# Board.net
KiCad netlist of a schematic drawn in EAGLE
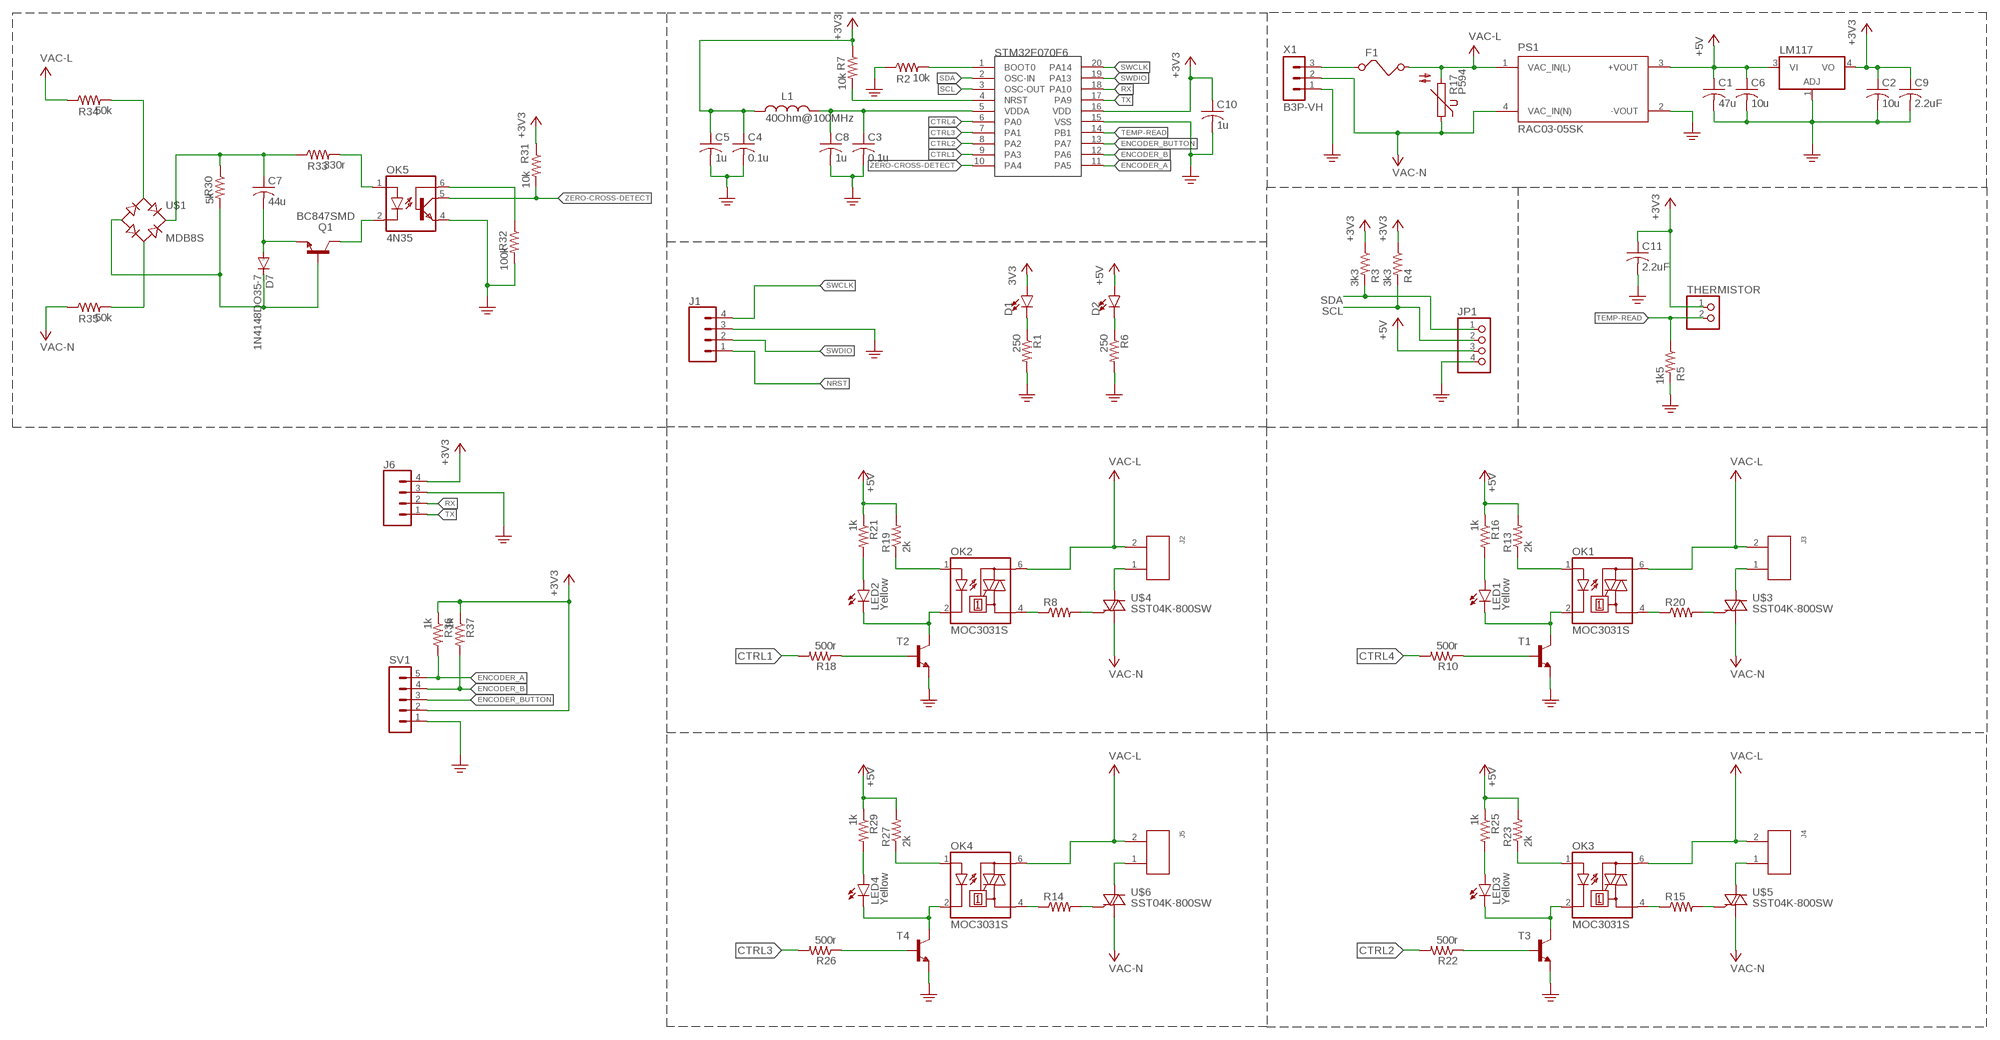
[diagram p0: schematic, sheet 1]

(export (version "E")
  (design (tool "Eeschema 10.0.6"))
  (components
    (comp (ref "C1")
      (value "47u")
      (footprint "eagle-import:C0603")
      (libsource (lib "eagle-import") (part "C-USC0603"))
    )
    (comp (ref "C2")
      (value "10u")
      (footprint "eagle-import:C0603")
      (libsource (lib "eagle-import") (part "C-USC0603"))
    )
    (comp (ref "C3")
      (value "0.1u")
      (footprint "eagle-import:C0603")
      (libsource (lib "eagle-import") (part "C-USC0603"))
    )
    (comp (ref "C4")
      (value "0.1u")
      (footprint "eagle-import:C0603")
      (libsource (lib "eagle-import") (part "C-USC0603"))
    )
    (comp (ref "C5")
      (value "1u")
      (footprint "eagle-import:C0603")
      (libsource (lib "eagle-import") (part "C-USC0603"))
    )
    (comp (ref "C6")
      (value "10u")
      (footprint "eagle-import:C0603")
      (libsource (lib "eagle-import") (part "C-USC0603"))
    )
    (comp (ref "C7")
      (value "44u")
      (footprint "eagle-import:C0603")
      (libsource (lib "eagle-import") (part "C-USC0603"))
    )
    (comp (ref "C8")
      (value "1u")
      (footprint "eagle-import:C0603")
      (libsource (lib "eagle-import") (part "C-USC0603"))
    )
    (comp (ref "C9")
      (value "2.2uF")
      (footprint "eagle-import:C0603")
      (libsource (lib "eagle-import") (part "C-USC0603"))
    )
    (comp (ref "C10")
      (value "1u")
      (footprint "eagle-import:C0603")
      (libsource (lib "eagle-import") (part "C-USC0603"))
    )
    (comp (ref "C11")
      (value "2.2uF")
      (footprint "eagle-import:C0603")
      (libsource (lib "eagle-import") (part "C-USC0603"))
    )
    (comp (ref "D1")
      (value "LED0603")
      (footprint "eagle-import:LED-0603")
      (libsource (lib "eagle-import") (part "LED0603"))
    )
    (comp (ref "D2")
      (value "LED0603")
      (footprint "eagle-import:LED-0603")
      (libsource (lib "eagle-import") (part "LED0603"))
    )
    (comp (ref "D7")
      (value "1N4148DO35-7")
      (footprint "eagle-import:DO35-7")
      (libsource (lib "eagle-import") (part "1N4148DO35-7"))
    )
    (comp (ref "F1")
      (value "FUSE")
      (footprint "eagle-import:FUSE")
      (libsource (lib "eagle-import") (part "FUSE"))
    )
    (comp (ref "J1")
      (value "CONN_04")
      (footprint "eagle-import:1X04")
      (libsource (lib "eagle-import") (part "CONN_04"))
    )
    (comp (ref "J2")
      (value "66100211622")
      (footprint "eagle-import:66100211622")
      (libsource (lib "eagle-import") (part "66100211622"))
    )
    (comp (ref "J3")
      (value "66100211622")
      (footprint "eagle-import:66100211622")
      (libsource (lib "eagle-import") (part "66100211622"))
    )
    (comp (ref "J4")
      (value "66100211622")
      (footprint "eagle-import:66100211622")
      (libsource (lib "eagle-import") (part "66100211622"))
    )
    (comp (ref "J5")
      (value "66100211622")
      (footprint "eagle-import:66100211622")
      (libsource (lib "eagle-import") (part "66100211622"))
    )
    (comp (ref "J6")
      (value "CONN_04")
      (footprint "eagle-import:1X04")
      (libsource (lib "eagle-import") (part "CONN_04"))
    )
    (comp (ref "JP1")
      (value "PINHD-1X4")
      (footprint "eagle-import:1X04")
      (libsource (lib "eagle-import") (part "PINHD-1X4"))
    )
    (comp (ref "L1")
      (value "40Ohm@100MHz")
      (footprint "eagle-import:WE-CBF_0805(W=3.0)")
      (libsource (lib "eagle-import") (part "WE-CBF_0805_WB_HS_74279208"))
    )
    (comp (ref "LED1")
      (value "Yellow")
      (footprint "eagle-import:LED-0603")
      (libsource (lib "eagle-import") (part "LED-YELLOW0603"))
    )
    (comp (ref "LED2")
      (value "Yellow")
      (footprint "eagle-import:LED-0603")
      (libsource (lib "eagle-import") (part "LED-YELLOW0603"))
    )
    (comp (ref "LED3")
      (value "Yellow")
      (footprint "eagle-import:LED-0603")
      (libsource (lib "eagle-import") (part "LED-YELLOW0603"))
    )
    (comp (ref "LED4")
      (value "Yellow")
      (footprint "eagle-import:LED-0603")
      (libsource (lib "eagle-import") (part "LED-YELLOW0603"))
    )
    (comp (ref "LM117")
      (value "317EMP")
      (footprint "eagle-import:SOT223")
      (libsource (lib "eagle-import") (part "317EMP"))
    )
    (comp (ref "OK1")
      (value "MOC3031S")
      (footprint "eagle-import:DIL6-SMD")
      (fields (field (name "MF") "FAIRCHILD SEMICONDUCTOR") (field (name "MPN") "MOC3031SM"))
      (libsource (lib "eagle-import") (part "MOC30S31"))
    )
    (comp (ref "OK2")
      (value "MOC3031S")
      (footprint "eagle-import:DIL6-SMD")
      (fields (field (name "MF") "FAIRCHILD SEMICONDUCTOR") (field (name "MPN") "MOC3031SM"))
      (libsource (lib "eagle-import") (part "MOC30S31"))
    )
    (comp (ref "OK3")
      (value "MOC3031S")
      (footprint "eagle-import:DIL6-SMD")
      (fields (field (name "MF") "FAIRCHILD SEMICONDUCTOR") (field (name "MPN") "MOC3031SM"))
      (libsource (lib "eagle-import") (part "MOC30S31"))
    )
    (comp (ref "OK4")
      (value "MOC3031S")
      (footprint "eagle-import:DIL6-SMD")
      (fields (field (name "MF") "FAIRCHILD SEMICONDUCTOR") (field (name "MPN") "MOC3031SM"))
      (libsource (lib "eagle-import") (part "MOC30S31"))
    )
    (comp (ref "OK5")
      (value "4N35")
      (footprint "eagle-import:DIL06")
      (fields (field (name "MF") "FAIRCHILD SEMICONDUCTOR"))
      (libsource (lib "eagle-import") (part "4N35"))
    )
    (comp (ref "PS1")
      (value "RAC03-05SK")
      (footprint "eagle-import:CONV_RAC03-05SK")
      (fields (field (name "MF") "Recom Power"))
      (libsource (lib "eagle-import") (part "RAC03-05SK"))
    )
    (comp (ref "Q1")
      (value "BC847SMD")
      (footprint "eagle-import:SOT23")
      (libsource (lib "eagle-import") (part "BC847SMD"))
    )
    (comp (ref "R1")
      (value "250")
      (footprint "eagle-import:R0603")
      (libsource (lib "eagle-import") (part "R-US_R0603"))
    )
    (comp (ref "R2")
      (value "10k")
      (footprint "eagle-import:R0603")
      (libsource (lib "eagle-import") (part "R-US_R0603"))
    )
    (comp (ref "R3")
      (value "3k3")
      (footprint "eagle-import:R0603")
      (libsource (lib "eagle-import") (part "R-US_R0603"))
    )
    (comp (ref "R4")
      (value "3k3")
      (footprint "eagle-import:R0603")
      (libsource (lib "eagle-import") (part "R-US_R0603"))
    )
    (comp (ref "R5")
      (value "1k5")
      (footprint "eagle-import:R0603")
      (libsource (lib "eagle-import") (part "R-US_R0603"))
    )
    (comp (ref "R6")
      (value "250")
      (footprint "eagle-import:R0603")
      (libsource (lib "eagle-import") (part "R-US_R0603"))
    )
    (comp (ref "R7")
      (value "10k")
      (footprint "eagle-import:R0603")
      (libsource (lib "eagle-import") (part "R-US_R0603"))
    )
    (comp (ref "R8")
      (value "R-US_0613/15")
      (footprint "eagle-import:P0613_15")
      (libsource (lib "eagle-import") (part "R-US_0613/15"))
    )
    (comp (ref "R10")
      (value "500r")
      (footprint "eagle-import:R0603")
      (libsource (lib "eagle-import") (part "R-US_R0603"))
    )
    (comp (ref "R13")
      (value "2k")
      (footprint "eagle-import:R0603")
      (libsource (lib "eagle-import") (part "R-US_R0603"))
    )
    (comp (ref "R14")
      (value "R-US_0613/15")
      (footprint "eagle-import:P0613_15")
      (libsource (lib "eagle-import") (part "R-US_0613/15"))
    )
    (comp (ref "R15")
      (value "R-US_0613/15")
      (footprint "eagle-import:P0613_15")
      (libsource (lib "eagle-import") (part "R-US_0613/15"))
    )
    (comp (ref "R16")
      (value "1k")
      (footprint "eagle-import:R0603")
      (libsource (lib "eagle-import") (part "R-US_R0603"))
    )
    (comp (ref "R17")
      (value "P594")
      (footprint "eagle-import:P594")
      (libsource (lib "eagle-import") (part "P594"))
    )
    (comp (ref "R18")
      (value "500r")
      (footprint "eagle-import:R0603")
      (libsource (lib "eagle-import") (part "R-US_R0603"))
    )
    (comp (ref "R19")
      (value "2k")
      (footprint "eagle-import:R0603")
      (libsource (lib "eagle-import") (part "R-US_R0603"))
    )
    (comp (ref "R20")
      (value "R-US_0613/15")
      (footprint "eagle-import:P0613_15")
      (libsource (lib "eagle-import") (part "R-US_0613/15"))
    )
    (comp (ref "R21")
      (value "1k")
      (footprint "eagle-import:R0603")
      (libsource (lib "eagle-import") (part "R-US_R0603"))
    )
    (comp (ref "R22")
      (value "500r")
      (footprint "eagle-import:R0603")
      (libsource (lib "eagle-import") (part "R-US_R0603"))
    )
    (comp (ref "R23")
      (value "2k")
      (footprint "eagle-import:R0603")
      (libsource (lib "eagle-import") (part "R-US_R0603"))
    )
    (comp (ref "R25")
      (value "1k")
      (footprint "eagle-import:R0603")
      (libsource (lib "eagle-import") (part "R-US_R0603"))
    )
    (comp (ref "R26")
      (value "500r")
      (footprint "eagle-import:R0603")
      (libsource (lib "eagle-import") (part "R-US_R0603"))
    )
    (comp (ref "R27")
      (value "2k")
      (footprint "eagle-import:R0603")
      (libsource (lib "eagle-import") (part "R-US_R0603"))
    )
    (comp (ref "R29")
      (value "1k")
      (footprint "eagle-import:R0603")
      (libsource (lib "eagle-import") (part "R-US_R0603"))
    )
    (comp (ref "R30")
      (value "5k")
      (footprint "eagle-import:R0603")
      (libsource (lib "eagle-import") (part "R-US_R0603"))
    )
    (comp (ref "R31")
      (value "10k")
      (footprint "eagle-import:R0603")
      (libsource (lib "eagle-import") (part "R-US_R0603"))
    )
    (comp (ref "R32")
      (value "100k")
      (footprint "eagle-import:R0603")
      (libsource (lib "eagle-import") (part "R-US_R0603"))
    )
    (comp (ref "R33")
      (value "330r")
      (footprint "eagle-import:R0603")
      (libsource (lib "eagle-import") (part "R-US_R0603"))
    )
    (comp (ref "R34")
      (value "50k")
      (footprint "eagle-import:R0603")
      (libsource (lib "eagle-import") (part "R-US_R0603"))
    )
    (comp (ref "R35")
      (value "50k")
      (footprint "eagle-import:R0603")
      (libsource (lib "eagle-import") (part "R-US_R0603"))
    )
    (comp (ref "R36")
      (value "1k")
      (footprint "eagle-import:R0603")
      (libsource (lib "eagle-import") (part "R-US_R0603"))
    )
    (comp (ref "R37")
      (value "1k")
      (footprint "eagle-import:R0603")
      (libsource (lib "eagle-import") (part "R-US_R0603"))
    )
    (comp (ref "STM32F070F6")
      (value "STM32F07")
      (footprint "eagle-import:TSSOP20")
      (libsource (lib "eagle-import") (part "STM32F07"))
    )
    (comp (ref "SV1")
      (value "MA05-1")
      (footprint "eagle-import:MA05-1")
      (libsource (lib "eagle-import") (part "MA05-1"))
    )
    (comp (ref "T1")
      (value "-NPN-SOT23-EBC")
      (footprint "eagle-import:SOT23-EBC")
      (libsource (lib "eagle-import") (part "-NPN-SOT23-EBC"))
    )
    (comp (ref "T2")
      (value "-NPN-SOT23-EBC")
      (footprint "eagle-import:SOT23-EBC")
      (libsource (lib "eagle-import") (part "-NPN-SOT23-EBC"))
    )
    (comp (ref "T3")
      (value "-NPN-SOT23-EBC")
      (footprint "eagle-import:SOT23-EBC")
      (libsource (lib "eagle-import") (part "-NPN-SOT23-EBC"))
    )
    (comp (ref "T4")
      (value "-NPN-SOT23-EBC")
      (footprint "eagle-import:SOT23-EBC")
      (libsource (lib "eagle-import") (part "-NPN-SOT23-EBC"))
    )
    (comp (ref "THERMISTOR")
      (value "PINHD-1X2")
      (footprint "eagle-import:1X02")
      (libsource (lib "eagle-import") (part "PINHD-1X2"))
    )
    (comp (ref "U$1")
      (value "MDB8S")
      (footprint "eagle-import:4-MICRODIP")
      (libsource (lib "eagle-import") (part "MDB8S"))
    )
    (comp (ref "U$3")
      (value "SST04K-800SW")
      (footprint "eagle-import:DPAK")
      (libsource (lib "eagle-import") (part "SST04K-800SW"))
    )
    (comp (ref "U$4")
      (value "SST04K-800SW")
      (footprint "eagle-import:DPAK")
      (libsource (lib "eagle-import") (part "SST04K-800SW"))
    )
    (comp (ref "U$5")
      (value "SST04K-800SW")
      (footprint "eagle-import:DPAK")
      (libsource (lib "eagle-import") (part "SST04K-800SW"))
    )
    (comp (ref "U$6")
      (value "SST04K-800SW")
      (footprint "eagle-import:DPAK")
      (libsource (lib "eagle-import") (part "SST04K-800SW"))
    )
    (comp (ref "X1")
      (value "B3P-VH")
      (footprint "eagle-import:B3P-VH")
      (libsource (lib "eagle-import") (part "B3P-VH"))
    )
  )
  (nets
    (net (code "1") (name "+3V3") (class "Default")
      (node (ref "C10") (pin "1") (pinfunction "1_1") (pintype "passive"))
      (node (ref "C11") (pin "1") (pinfunction "1_1") (pintype "passive"))
      (node (ref "C2") (pin "1") (pinfunction "1_1") (pintype "passive"))
      (node (ref "C4") (pin "1") (pinfunction "1_1") (pintype "passive"))
      (node (ref "C5") (pin "1") (pinfunction "1_1") (pintype "passive"))
      (node (ref "C9") (pin "1") (pinfunction "1_1") (pintype "passive"))
      (node (ref "D1") (pin "A") (pinfunction "A_A") (pintype "passive"))
      (node (ref "J6") (pin "4") (pinfunction "4_4") (pintype "passive"))
      (node (ref "L1") (pin "1") (pinfunction "1_1") (pintype "passive"))
      (node (ref "LM117") (pin "4") (pinfunction "VO_4") (pintype "passive"))
      (node (ref "R3") (pin "1") (pinfunction "1_1") (pintype "passive"))
      (node (ref "R31") (pin "1") (pinfunction "1_1") (pintype "passive"))
      (node (ref "R36") (pin "1") (pinfunction "1_1") (pintype "passive"))
      (node (ref "R37") (pin "1") (pinfunction "1_1") (pintype "passive"))
      (node (ref "R4") (pin "1") (pinfunction "1_1") (pintype "passive"))
      (node (ref "R7") (pin "1") (pinfunction "1_1") (pintype "passive"))
      (node (ref "STM32F070F6") (pin "16") (pinfunction "VDD_16") (pintype "bidirectional"))
      (node (ref "SV1") (pin "2") (pinfunction "2_2") (pintype "passive"))
      (node (ref "THERMISTOR") (pin "1") (pinfunction "1_1") (pintype "passive"))
    )
    (net (code "2") (name "+5V") (class "Default")
      (node (ref "C1") (pin "1") (pinfunction "1_1") (pintype "passive"))
      (node (ref "C6") (pin "1") (pinfunction "1_1") (pintype "passive"))
      (node (ref "D2") (pin "A") (pinfunction "A_A") (pintype "passive"))
      (node (ref "JP1") (pin "3") (pinfunction "3_3") (pintype "passive"))
      (node (ref "LM117") (pin "3") (pinfunction "VI_3") (pintype "input"))
      (node (ref "PS1") (pin "3") (pinfunction "+VOUT_3") (pintype "output"))
      (node (ref "R13") (pin "2") (pinfunction "2_2") (pintype "passive"))
      (node (ref "R16") (pin "1") (pinfunction "1_1") (pintype "passive"))
      (node (ref "R19") (pin "2") (pinfunction "2_2") (pintype "passive"))
      (node (ref "R21") (pin "1") (pinfunction "1_1") (pintype "passive"))
      (node (ref "R23") (pin "2") (pinfunction "2_2") (pintype "passive"))
      (node (ref "R25") (pin "1") (pinfunction "1_1") (pintype "passive"))
      (node (ref "R27") (pin "2") (pinfunction "2_2") (pintype "passive"))
      (node (ref "R29") (pin "1") (pinfunction "1_1") (pintype "passive"))
    )
    (net (code "3") (name "CTRL1") (class "Default")
      (node (ref "R18") (pin "2") (pinfunction "2_2") (pintype "passive"))
      (node (ref "STM32F070F6") (pin "9") (pinfunction "PA3_9") (pintype "bidirectional"))
    )
    (net (code "4") (name "CTRL2") (class "Default")
      (node (ref "R22") (pin "2") (pinfunction "2_2") (pintype "passive"))
      (node (ref "STM32F070F6") (pin "8") (pinfunction "PA2_8") (pintype "bidirectional"))
    )
    (net (code "5") (name "CTRL3") (class "Default")
      (node (ref "R26") (pin "2") (pinfunction "2_2") (pintype "passive"))
      (node (ref "STM32F070F6") (pin "7") (pinfunction "PA1_7") (pintype "bidirectional"))
    )
    (net (code "6") (name "CTRL4") (class "Default")
      (node (ref "R10") (pin "2") (pinfunction "2_2") (pintype "passive"))
      (node (ref "STM32F070F6") (pin "6") (pinfunction "PA0_6") (pintype "bidirectional"))
    )
    (net (code "7") (name "ENCODER_A") (class "Default")
      (node (ref "R36") (pin "2") (pinfunction "2_2") (pintype "passive"))
      (node (ref "STM32F070F6") (pin "11") (pinfunction "PA5_11") (pintype "bidirectional"))
      (node (ref "SV1") (pin "5") (pinfunction "5_5") (pintype "passive"))
    )
    (net (code "8") (name "ENCODER_B") (class "Default")
      (node (ref "R37") (pin "2") (pinfunction "2_2") (pintype "passive"))
      (node (ref "STM32F070F6") (pin "12") (pinfunction "PA6_12") (pintype "bidirectional"))
      (node (ref "SV1") (pin "4") (pinfunction "4_4") (pintype "passive"))
    )
    (net (code "9") (name "ENCODER_BUTTON") (class "Default")
      (node (ref "STM32F070F6") (pin "13") (pinfunction "PA7_13") (pintype "bidirectional"))
      (node (ref "SV1") (pin "3") (pinfunction "3_3") (pintype "passive"))
    )
    (net (code "10") (name "NRST") (class "Default")
      (node (ref "J1") (pin "1") (pinfunction "1_1") (pintype "passive"))
      (node (ref "R7") (pin "2") (pinfunction "2_2") (pintype "passive"))
      (node (ref "STM32F070F6") (pin "4") (pinfunction "NRST_4") (pintype "bidirectional"))
    )
    (net (code "11") (name "Net-(D1-PadC)") (class "Default")
      (node (ref "D1") (pin "C") (pinfunction "C_C") (pintype "passive"))
      (node (ref "R1") (pin "1") (pinfunction "1_1") (pintype "passive"))
    )
    (net (code "12") (name "Net-(D2-PadC)") (class "Default")
      (node (ref "D2") (pin "C") (pinfunction "C_C") (pintype "passive"))
      (node (ref "R6") (pin "1") (pinfunction "1_1") (pintype "passive"))
    )
    (net (code "13") (name "Net-(F1-Pad1)") (class "Default")
      (node (ref "F1") (pin "1") (pinfunction "1_1") (pintype "passive"))
      (node (ref "X1") (pin "3") (pinfunction "3_3") (pintype "passive"))
    )
    (net (code "14") (name "Net-(LED1-PadA)") (class "Default")
      (node (ref "LED1") (pin "A") (pinfunction "A_A") (pintype "passive"))
      (node (ref "R16") (pin "2") (pinfunction "2_2") (pintype "passive"))
    )
    (net (code "15") (name "Net-(LED2-PadA)") (class "Default")
      (node (ref "LED2") (pin "A") (pinfunction "A_A") (pintype "passive"))
      (node (ref "R21") (pin "2") (pinfunction "2_2") (pintype "passive"))
    )
    (net (code "16") (name "Net-(LED3-PadA)") (class "Default")
      (node (ref "LED3") (pin "A") (pinfunction "A_A") (pintype "passive"))
      (node (ref "R25") (pin "2") (pinfunction "2_2") (pintype "passive"))
    )
    (net (code "17") (name "Net-(LED4-PadA)") (class "Default")
      (node (ref "LED4") (pin "A") (pinfunction "A_A") (pintype "passive"))
      (node (ref "R29") (pin "2") (pinfunction "2_2") (pintype "passive"))
    )
    (net (code "18") (name "Net-(OK1-A)") (class "Default")
      (node (ref "OK1") (pin "1") (pinfunction "A_1") (pintype "passive"))
      (node (ref "R13") (pin "1") (pinfunction "1_1") (pintype "passive"))
    )
    (net (code "19") (name "Net-(OK1-A1)") (class "Default")
      (node (ref "OK1") (pin "4") (pinfunction "A1_4") (pintype "passive"))
      (node (ref "R20") (pin "1") (pinfunction "1_1") (pintype "passive"))
    )
    (net (code "20") (name "Net-(OK1-C)") (class "Default")
      (node (ref "LED1") (pin "C") (pinfunction "C_C") (pintype "passive"))
      (node (ref "OK1") (pin "2") (pinfunction "C_2") (pintype "passive"))
      (node (ref "T1") (pin "C") (pinfunction "C_C") (pintype "passive"))
    )
    (net (code "21") (name "Net-(OK2-A)") (class "Default")
      (node (ref "OK2") (pin "1") (pinfunction "A_1") (pintype "passive"))
      (node (ref "R19") (pin "1") (pinfunction "1_1") (pintype "passive"))
    )
    (net (code "22") (name "Net-(OK2-A1)") (class "Default")
      (node (ref "OK2") (pin "4") (pinfunction "A1_4") (pintype "passive"))
      (node (ref "R8") (pin "1") (pinfunction "1_1") (pintype "passive"))
    )
    (net (code "23") (name "Net-(OK2-C)") (class "Default")
      (node (ref "LED2") (pin "C") (pinfunction "C_C") (pintype "passive"))
      (node (ref "OK2") (pin "2") (pinfunction "C_2") (pintype "passive"))
      (node (ref "T2") (pin "C") (pinfunction "C_C") (pintype "passive"))
    )
    (net (code "24") (name "Net-(OK3-A)") (class "Default")
      (node (ref "OK3") (pin "1") (pinfunction "A_1") (pintype "passive"))
      (node (ref "R23") (pin "1") (pinfunction "1_1") (pintype "passive"))
    )
    (net (code "25") (name "Net-(OK3-A1)") (class "Default")
      (node (ref "OK3") (pin "4") (pinfunction "A1_4") (pintype "passive"))
      (node (ref "R15") (pin "1") (pinfunction "1_1") (pintype "passive"))
    )
    (net (code "26") (name "Net-(OK3-C)") (class "Default")
      (node (ref "LED3") (pin "C") (pinfunction "C_C") (pintype "passive"))
      (node (ref "OK3") (pin "2") (pinfunction "C_2") (pintype "passive"))
      (node (ref "T3") (pin "C") (pinfunction "C_C") (pintype "passive"))
    )
    (net (code "27") (name "Net-(OK4-A)") (class "Default")
      (node (ref "OK4") (pin "1") (pinfunction "A_1") (pintype "passive"))
      (node (ref "R27") (pin "1") (pinfunction "1_1") (pintype "passive"))
    )
    (net (code "28") (name "Net-(OK4-A1)") (class "Default")
      (node (ref "OK4") (pin "4") (pinfunction "A1_4") (pintype "passive"))
      (node (ref "R14") (pin "1") (pinfunction "1_1") (pintype "passive"))
    )
    (net (code "29") (name "Net-(OK4-C)") (class "Default")
      (node (ref "LED4") (pin "C") (pinfunction "C_C") (pintype "passive"))
      (node (ref "OK4") (pin "2") (pinfunction "C_2") (pintype "passive"))
      (node (ref "T4") (pin "C") (pinfunction "C_C") (pintype "passive"))
    )
    (net (code "30") (name "Net-(OK5-A)") (class "Default")
      (node (ref "OK5") (pin "1") (pinfunction "A_1") (pintype "passive"))
      (node (ref "R33") (pin "2") (pinfunction "2_2") (pintype "passive"))
    )
    (net (code "31") (name "Net-(OK5-BAS)") (class "Default")
      (node (ref "OK5") (pin "6") (pinfunction "BAS_6") (pintype "passive"))
      (node (ref "R32") (pin "1") (pinfunction "1_1") (pintype "passive"))
    )
    (net (code "32") (name "Net-(OK5-C)") (class "Default")
      (node (ref "OK5") (pin "2") (pinfunction "C_2") (pintype "passive"))
      (node (ref "Q1") (pin "3") (pinfunction "C_3") (pintype "passive"))
    )
    (net (code "33") (name "Net-(Q1-B)") (class "Default")
      (node (ref "D7") (pin "C") (pinfunction "C_C") (pintype "passive"))
      (node (ref "Q1") (pin "1") (pinfunction "B_1") (pintype "passive"))
      (node (ref "R30") (pin "2") (pinfunction "2_2") (pintype "passive"))
      (node (ref "U$1") (pin "4") (pinfunction "-_4") (pintype "passive"))
    )
    (net (code "34") (name "Net-(Q1-E)") (class "Default")
      (node (ref "C7") (pin "2") (pinfunction "2_2") (pintype "passive"))
      (node (ref "D7") (pin "A") (pinfunction "A_A") (pintype "passive"))
      (node (ref "Q1") (pin "2") (pinfunction "E_2") (pintype "passive"))
    )
    (net (code "35") (name "Net-(R10-Pad1)") (class "Default")
      (node (ref "R10") (pin "1") (pinfunction "1_1") (pintype "passive"))
      (node (ref "T1") (pin "B") (pinfunction "B_B") (pintype "passive"))
    )
    (net (code "36") (name "Net-(R18-Pad1)") (class "Default")
      (node (ref "R18") (pin "1") (pinfunction "1_1") (pintype "passive"))
      (node (ref "T2") (pin "B") (pinfunction "B_B") (pintype "passive"))
    )
    (net (code "37") (name "Net-(R22-Pad1)") (class "Default")
      (node (ref "R22") (pin "1") (pinfunction "1_1") (pintype "passive"))
      (node (ref "T3") (pin "B") (pinfunction "B_B") (pintype "passive"))
    )
    (net (code "38") (name "Net-(R26-Pad1)") (class "Default")
      (node (ref "R26") (pin "1") (pinfunction "1_1") (pintype "passive"))
      (node (ref "T4") (pin "B") (pinfunction "B_B") (pintype "passive"))
    )
    (net (code "39") (name "Net-(STM32F070F6-BOOT0)") (class "Default")
      (node (ref "R2") (pin "2") (pinfunction "2_2") (pintype "passive"))
      (node (ref "STM32F070F6") (pin "1") (pinfunction "BOOT0_1") (pintype "bidirectional"))
    )
    (net (code "40") (name "Net-(STM32F070F6-VDDA)") (class "Default")
      (node (ref "C3") (pin "1") (pinfunction "1_1") (pintype "passive"))
      (node (ref "C8") (pin "1") (pinfunction "1_1") (pintype "passive"))
      (node (ref "L1") (pin "2") (pinfunction "2_2") (pintype "passive"))
      (node (ref "STM32F070F6") (pin "5") (pinfunction "VDDA_5") (pintype "bidirectional"))
    )
    (net (code "41") (name "Net-(U$1-+)") (class "Default")
      (node (ref "C7") (pin "1") (pinfunction "1_1") (pintype "passive"))
      (node (ref "R30") (pin "1") (pinfunction "1_1") (pintype "passive"))
      (node (ref "R33") (pin "1") (pinfunction "1_1") (pintype "passive"))
      (node (ref "U$1") (pin "3") (pinfunction "+_3") (pintype "passive"))
    )
    (net (code "42") (name "Net-(U$1-AC1)") (class "Default")
      (node (ref "R34") (pin "2") (pinfunction "2_2") (pintype "passive"))
      (node (ref "U$1") (pin "1") (pinfunction "AC1_1") (pintype "passive"))
    )
    (net (code "43") (name "Net-(U$1-AC2)") (class "Default")
      (node (ref "R35") (pin "2") (pinfunction "2_2") (pintype "passive"))
      (node (ref "U$1") (pin "2") (pinfunction "AC2_2") (pintype "passive"))
    )
    (net (code "44") (name "Net-(U$3-A2)") (class "Default")
      (node (ref "J3") (pin "1") (pinfunction "1_1") (pintype "passive"))
      (node (ref "U$3") (pin "4") (pinfunction "A2_4") (pintype "passive"))
    )
    (net (code "45") (name "Net-(U$3-G)") (class "Default")
      (node (ref "R20") (pin "2") (pinfunction "2_2") (pintype "passive"))
      (node (ref "U$3") (pin "3") (pinfunction "G_3") (pintype "passive"))
    )
    (net (code "46") (name "Net-(U$4-A2)") (class "Default")
      (node (ref "J2") (pin "1") (pinfunction "1_1") (pintype "passive"))
      (node (ref "U$4") (pin "4") (pinfunction "A2_4") (pintype "passive"))
    )
    (net (code "47") (name "Net-(U$4-G)") (class "Default")
      (node (ref "R8") (pin "2") (pinfunction "2_2") (pintype "passive"))
      (node (ref "U$4") (pin "3") (pinfunction "G_3") (pintype "passive"))
    )
    (net (code "48") (name "Net-(U$5-A2)") (class "Default")
      (node (ref "J4") (pin "1") (pinfunction "1_1") (pintype "passive"))
      (node (ref "U$5") (pin "4") (pinfunction "A2_4") (pintype "passive"))
    )
    (net (code "49") (name "Net-(U$5-G)") (class "Default")
      (node (ref "R15") (pin "2") (pinfunction "2_2") (pintype "passive"))
      (node (ref "U$5") (pin "3") (pinfunction "G_3") (pintype "passive"))
    )
    (net (code "50") (name "Net-(U$6-A2)") (class "Default")
      (node (ref "J5") (pin "1") (pinfunction "1_1") (pintype "passive"))
      (node (ref "U$6") (pin "4") (pinfunction "A2_4") (pintype "passive"))
    )
    (net (code "51") (name "Net-(U$6-G)") (class "Default")
      (node (ref "R14") (pin "2") (pinfunction "2_2") (pintype "passive"))
      (node (ref "U$6") (pin "3") (pinfunction "G_3") (pintype "passive"))
    )
    (net (code "52") (name "PE") (class "Default")
      (node (ref "C1") (pin "2") (pinfunction "2_2") (pintype "passive"))
      (node (ref "C10") (pin "2") (pinfunction "2_2") (pintype "passive"))
      (node (ref "C11") (pin "2") (pinfunction "2_2") (pintype "passive"))
      (node (ref "C2") (pin "2") (pinfunction "2_2") (pintype "passive"))
      (node (ref "C3") (pin "2") (pinfunction "2_2") (pintype "passive"))
      (node (ref "C4") (pin "2") (pinfunction "2_2") (pintype "passive"))
      (node (ref "C5") (pin "2") (pinfunction "2_2") (pintype "passive"))
      (node (ref "C6") (pin "2") (pinfunction "2_2") (pintype "passive"))
      (node (ref "C8") (pin "2") (pinfunction "2_2") (pintype "passive"))
      (node (ref "C9") (pin "2") (pinfunction "2_2") (pintype "passive"))
      (node (ref "J1") (pin "3") (pinfunction "3_3") (pintype "passive"))
      (node (ref "J6") (pin "3") (pinfunction "3_3") (pintype "passive"))
      (node (ref "JP1") (pin "4") (pinfunction "4_4") (pintype "passive"))
      (node (ref "LM117") (pin "1") (pinfunction "ADJ_1") (pintype "input"))
      (node (ref "OK5") (pin "4") (pinfunction "EMI_4") (pintype "passive"))
      (node (ref "PS1") (pin "2") (pinfunction "-VOUT_2") (pintype "output"))
      (node (ref "R1") (pin "2") (pinfunction "2_2") (pintype "passive"))
      (node (ref "R2") (pin "1") (pinfunction "1_1") (pintype "passive"))
      (node (ref "R32") (pin "2") (pinfunction "2_2") (pintype "passive"))
      (node (ref "R5") (pin "2") (pinfunction "2_2") (pintype "passive"))
      (node (ref "R6") (pin "2") (pinfunction "2_2") (pintype "passive"))
      (node (ref "STM32F070F6") (pin "15") (pinfunction "VSS_15") (pintype "bidirectional"))
      (node (ref "SV1") (pin "1") (pinfunction "1_1") (pintype "passive"))
      (node (ref "T1") (pin "E") (pinfunction "E_E") (pintype "passive"))
      (node (ref "T2") (pin "E") (pinfunction "E_E") (pintype "passive"))
      (node (ref "T3") (pin "E") (pinfunction "E_E") (pintype "passive"))
      (node (ref "T4") (pin "E") (pinfunction "E_E") (pintype "passive"))
      (node (ref "X1") (pin "1") (pinfunction "1_1") (pintype "passive"))
    )
    (net (code "53") (name "RX") (class "Default")
      (node (ref "J6") (pin "2") (pinfunction "2_2") (pintype "passive"))
      (node (ref "STM32F070F6") (pin "18") (pinfunction "PA10_18") (pintype "bidirectional"))
    )
    (net (code "54") (name "SCL") (class "Default")
      (node (ref "JP1") (pin "2") (pinfunction "2_2") (pintype "passive"))
      (node (ref "R4") (pin "2") (pinfunction "2_2") (pintype "passive"))
      (node (ref "STM32F070F6") (pin "3") (pinfunction "OSC-OUT_3") (pintype "bidirectional"))
    )
    (net (code "55") (name "SDA") (class "Default")
      (node (ref "JP1") (pin "1") (pinfunction "1_1") (pintype "passive"))
      (node (ref "R3") (pin "2") (pinfunction "2_2") (pintype "passive"))
      (node (ref "STM32F070F6") (pin "2") (pinfunction "OSC-IN_2") (pintype "bidirectional"))
    )
    (net (code "56") (name "SWCLK") (class "Default")
      (node (ref "J1") (pin "4") (pinfunction "4_4") (pintype "passive"))
      (node (ref "STM32F070F6") (pin "20") (pinfunction "PA14_20") (pintype "bidirectional"))
    )
    (net (code "57") (name "SWDIO") (class "Default")
      (node (ref "J1") (pin "2") (pinfunction "2_2") (pintype "passive"))
      (node (ref "STM32F070F6") (pin "19") (pinfunction "PA13_19") (pintype "bidirectional"))
    )
    (net (code "58") (name "TEMP-READ") (class "Default")
      (node (ref "R5") (pin "1") (pinfunction "1_1") (pintype "passive"))
      (node (ref "STM32F070F6") (pin "14") (pinfunction "PB1_14") (pintype "bidirectional"))
      (node (ref "THERMISTOR") (pin "2") (pinfunction "2_2") (pintype "passive"))
    )
    (net (code "59") (name "TX") (class "Default")
      (node (ref "J6") (pin "1") (pinfunction "1_1") (pintype "passive"))
      (node (ref "STM32F070F6") (pin "17") (pinfunction "PA9_17") (pintype "bidirectional"))
    )
    (net (code "60") (name "VAC-L") (class "Default")
      (node (ref "F1") (pin "2") (pinfunction "2_2") (pintype "passive"))
      (node (ref "J2") (pin "2") (pinfunction "2_2") (pintype "passive"))
      (node (ref "J3") (pin "2") (pinfunction "2_2") (pintype "passive"))
      (node (ref "J4") (pin "2") (pinfunction "2_2") (pintype "passive"))
      (node (ref "J5") (pin "2") (pinfunction "2_2") (pintype "passive"))
      (node (ref "OK1") (pin "6") (pinfunction "A2_6") (pintype "passive"))
      (node (ref "OK2") (pin "6") (pinfunction "A2_6") (pintype "passive"))
      (node (ref "OK3") (pin "6") (pinfunction "A2_6") (pintype "passive"))
      (node (ref "OK4") (pin "6") (pinfunction "A2_6") (pintype "passive"))
      (node (ref "PS1") (pin "1") (pinfunction "VAC_IN(L)_1") (pintype "input"))
      (node (ref "R17") (pin "2") (pinfunction "2_2") (pintype "passive"))
      (node (ref "R34") (pin "1") (pinfunction "1_1") (pintype "passive"))
    )
    (net (code "61") (name "VAC-N") (class "Default")
      (node (ref "PS1") (pin "4") (pinfunction "VAC_IN(N)_4") (pintype "input"))
      (node (ref "R17") (pin "1") (pinfunction "1_1") (pintype "passive"))
      (node (ref "R35") (pin "1") (pinfunction "1_1") (pintype "passive"))
      (node (ref "U$3") (pin "1") (pinfunction "A1_1") (pintype "passive"))
      (node (ref "U$4") (pin "1") (pinfunction "A1_1") (pintype "passive"))
      (node (ref "U$5") (pin "1") (pinfunction "A1_1") (pintype "passive"))
      (node (ref "U$6") (pin "1") (pinfunction "A1_1") (pintype "passive"))
      (node (ref "X1") (pin "2") (pinfunction "2_2") (pintype "passive"))
    )
    (net (code "62") (name "ZERO-CROSS-DETECT") (class "Default")
      (node (ref "OK5") (pin "5") (pinfunction "COL_5") (pintype "passive"))
      (node (ref "R31") (pin "2") (pinfunction "2_2") (pintype "passive"))
      (node (ref "STM32F070F6") (pin "10") (pinfunction "PA4_10") (pintype "bidirectional"))
    )
  )
)
